# FAN-plus-SHIM.net
KiCad netlist of a schematic drawn in EAGLE
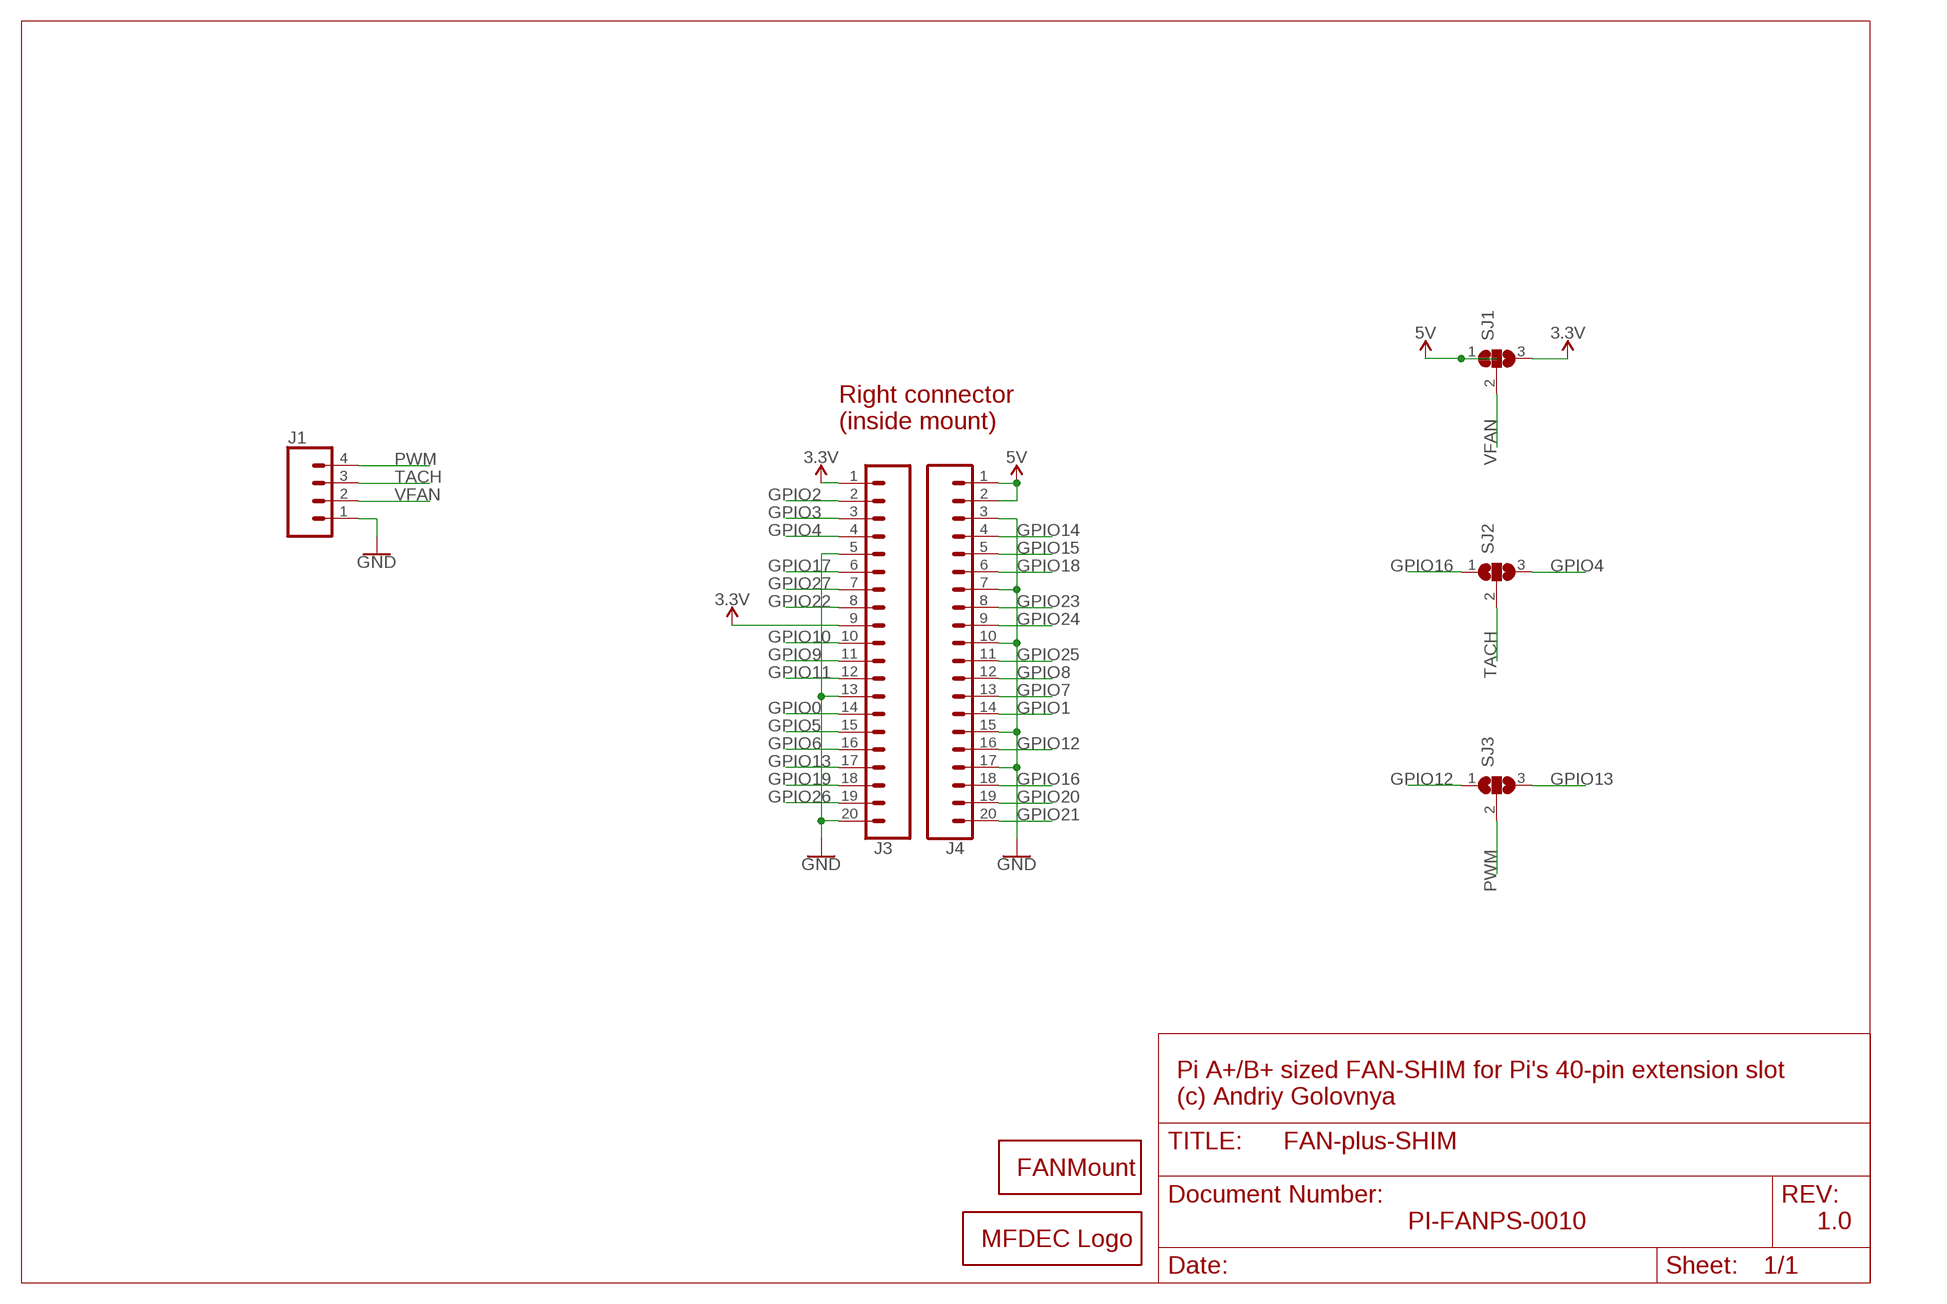
[diagram p0: schematic, sheet 1]

(export (version "E")
  (design (tool "Eeschema 10.0.6"))
  (components
    (comp (ref "FAN1")
      (value "FAN40HO")
      (footprint "eagle-import:FAN40HO")
      (libsource (lib "eagle-import") (part "FAN40HO"))
    )
    (comp (ref "J1")
      (value "CONN_04")
      (footprint "eagle-import:1X04")
      (libsource (lib "eagle-import") (part "CONN_04"))
    )
    (comp (ref "J3")
      (value "CONN_20LOCK")
      (footprint "eagle-import:1X20_LOCK")
      (libsource (lib "eagle-import") (part "CONN_20LOCK"))
    )
    (comp (ref "J4")
      (value "CONN_20LOCK")
      (footprint "eagle-import:1X20_LOCK")
      (libsource (lib "eagle-import") (part "CONN_20LOCK"))
    )
    (comp (ref "LOGO1")
      (value "MFDECLOGO_L_40MM")
      (footprint "eagle-import:MFDEC_L_40MM")
      (libsource (lib "eagle-import") (part "MFDECLOGO_L_40MM"))
    )
    (comp (ref "SJ1")
      (value "SJ2")
      (footprint "eagle-import:SJ_2")
      (libsource (lib "eagle-import") (part "SJ2"))
    )
    (comp (ref "SJ2")
      (value "SJ2")
      (footprint "eagle-import:SJ_2")
      (libsource (lib "eagle-import") (part "SJ2"))
    )
    (comp (ref "SJ3")
      (value "SJ2")
      (footprint "eagle-import:SJ_2")
      (libsource (lib "eagle-import") (part "SJ2"))
    )
  )
  (nets
    (net (code "1") (name "/GPIO0") (class "Default")
      (node (ref "J3") (pin "14") (pinfunction "14_14") (pintype "passive"))
    )
    (net (code "2") (name "/GPIO1") (class "Default")
      (node (ref "J4") (pin "14") (pinfunction "14_14") (pintype "passive"))
    )
    (net (code "3") (name "/GPIO2") (class "Default")
      (node (ref "J3") (pin "2") (pinfunction "2_2") (pintype "passive"))
    )
    (net (code "4") (name "/GPIO3") (class "Default")
      (node (ref "J3") (pin "3") (pinfunction "3_3") (pintype "passive"))
    )
    (net (code "5") (name "/GPIO4") (class "Default")
      (node (ref "J3") (pin "4") (pinfunction "4_4") (pintype "passive"))
      (node (ref "SJ2") (pin "3") (pinfunction "3_3") (pintype "passive"))
    )
    (net (code "6") (name "/GPIO5") (class "Default")
      (node (ref "J3") (pin "15") (pinfunction "15_15") (pintype "passive"))
    )
    (net (code "7") (name "/GPIO6") (class "Default")
      (node (ref "J3") (pin "16") (pinfunction "16_16") (pintype "passive"))
    )
    (net (code "8") (name "/GPIO7") (class "Default")
      (node (ref "J4") (pin "13") (pinfunction "13_13") (pintype "passive"))
    )
    (net (code "9") (name "/GPIO8") (class "Default")
      (node (ref "J4") (pin "12") (pinfunction "12_12") (pintype "passive"))
    )
    (net (code "10") (name "/GPIO9") (class "Default")
      (node (ref "J3") (pin "11") (pinfunction "11_11") (pintype "passive"))
    )
    (net (code "11") (name "/GPIO10") (class "Default")
      (node (ref "J3") (pin "10") (pinfunction "10_10") (pintype "passive"))
    )
    (net (code "12") (name "/GPIO11") (class "Default")
      (node (ref "J3") (pin "12") (pinfunction "12_12") (pintype "passive"))
    )
    (net (code "13") (name "/GPIO12") (class "Default")
      (node (ref "J4") (pin "16") (pinfunction "16_16") (pintype "passive"))
      (node (ref "SJ3") (pin "1") (pinfunction "1_1") (pintype "passive"))
    )
    (net (code "14") (name "/GPIO13") (class "Default")
      (node (ref "J3") (pin "17") (pinfunction "17_17") (pintype "passive"))
      (node (ref "SJ3") (pin "3") (pinfunction "3_3") (pintype "passive"))
    )
    (net (code "15") (name "/GPIO14") (class "Default")
      (node (ref "J4") (pin "4") (pinfunction "4_4") (pintype "passive"))
    )
    (net (code "16") (name "/GPIO15") (class "Default")
      (node (ref "J4") (pin "5") (pinfunction "5_5") (pintype "passive"))
    )
    (net (code "17") (name "/GPIO16") (class "Default")
      (node (ref "J4") (pin "18") (pinfunction "18_18") (pintype "passive"))
      (node (ref "SJ2") (pin "1") (pinfunction "1_1") (pintype "passive"))
    )
    (net (code "18") (name "/GPIO17") (class "Default")
      (node (ref "J3") (pin "6") (pinfunction "6_6") (pintype "passive"))
    )
    (net (code "19") (name "/GPIO18") (class "Default")
      (node (ref "J4") (pin "6") (pinfunction "6_6") (pintype "passive"))
    )
    (net (code "20") (name "/GPIO19") (class "Default")
      (node (ref "J3") (pin "18") (pinfunction "18_18") (pintype "passive"))
    )
    (net (code "21") (name "/GPIO20") (class "Default")
      (node (ref "J4") (pin "19") (pinfunction "19_19") (pintype "passive"))
    )
    (net (code "22") (name "/GPIO21") (class "Default")
      (node (ref "J4") (pin "20") (pinfunction "20_20") (pintype "passive"))
    )
    (net (code "23") (name "/GPIO22") (class "Default")
      (node (ref "J3") (pin "8") (pinfunction "8_8") (pintype "passive"))
    )
    (net (code "24") (name "/GPIO23") (class "Default")
      (node (ref "J4") (pin "8") (pinfunction "8_8") (pintype "passive"))
    )
    (net (code "25") (name "/GPIO24") (class "Default")
      (node (ref "J4") (pin "9") (pinfunction "9_9") (pintype "passive"))
    )
    (net (code "26") (name "/GPIO25") (class "Default")
      (node (ref "J4") (pin "11") (pinfunction "11_11") (pintype "passive"))
    )
    (net (code "27") (name "/GPIO26") (class "Default")
      (node (ref "J3") (pin "19") (pinfunction "19_19") (pintype "passive"))
    )
    (net (code "28") (name "/GPIO27") (class "Default")
      (node (ref "J3") (pin "7") (pinfunction "7_7") (pintype "passive"))
    )
    (net (code "29") (name "/PWM") (class "Default")
      (node (ref "J1") (pin "4") (pinfunction "4_4") (pintype "passive"))
      (node (ref "SJ3") (pin "2") (pinfunction "2_2") (pintype "passive"))
    )
    (net (code "30") (name "/TACH") (class "Default")
      (node (ref "J1") (pin "3") (pinfunction "3_3") (pintype "passive"))
      (node (ref "SJ2") (pin "2") (pinfunction "2_2") (pintype "passive"))
    )
    (net (code "31") (name "/VFAN") (class "Default")
      (node (ref "J1") (pin "2") (pinfunction "2_2") (pintype "passive"))
      (node (ref "SJ1") (pin "2") (pinfunction "2_2") (pintype "passive"))
    )
    (net (code "32") (name "3.3V") (class "Default")
      (node (ref "J3") (pin "1") (pinfunction "1_1") (pintype "passive"))
      (node (ref "J3") (pin "9") (pinfunction "9_9") (pintype "passive"))
      (node (ref "SJ1") (pin "3") (pinfunction "3_3") (pintype "passive"))
    )
    (net (code "33") (name "5V") (class "Default")
      (node (ref "J4") (pin "1") (pinfunction "1_1") (pintype "passive"))
      (node (ref "J4") (pin "2") (pinfunction "2_2") (pintype "passive"))
      (node (ref "SJ1") (pin "1") (pinfunction "1_1") (pintype "passive"))
    )
    (net (code "34") (name "GND") (class "Default")
      (node (ref "J1") (pin "1") (pinfunction "1_1") (pintype "passive"))
      (node (ref "J3") (pin "13") (pinfunction "13_13") (pintype "passive"))
      (node (ref "J3") (pin "20") (pinfunction "20_20") (pintype "passive"))
      (node (ref "J3") (pin "5") (pinfunction "5_5") (pintype "passive"))
      (node (ref "J4") (pin "10") (pinfunction "10_10") (pintype "passive"))
      (node (ref "J4") (pin "15") (pinfunction "15_15") (pintype "passive"))
      (node (ref "J4") (pin "17") (pinfunction "17_17") (pintype "passive"))
      (node (ref "J4") (pin "3") (pinfunction "3_3") (pintype "passive"))
      (node (ref "J4") (pin "7") (pinfunction "7_7") (pintype "passive"))
    )
  )
)
